# pcbremote.net
KiCad netlist of a schematic drawn in EAGLE
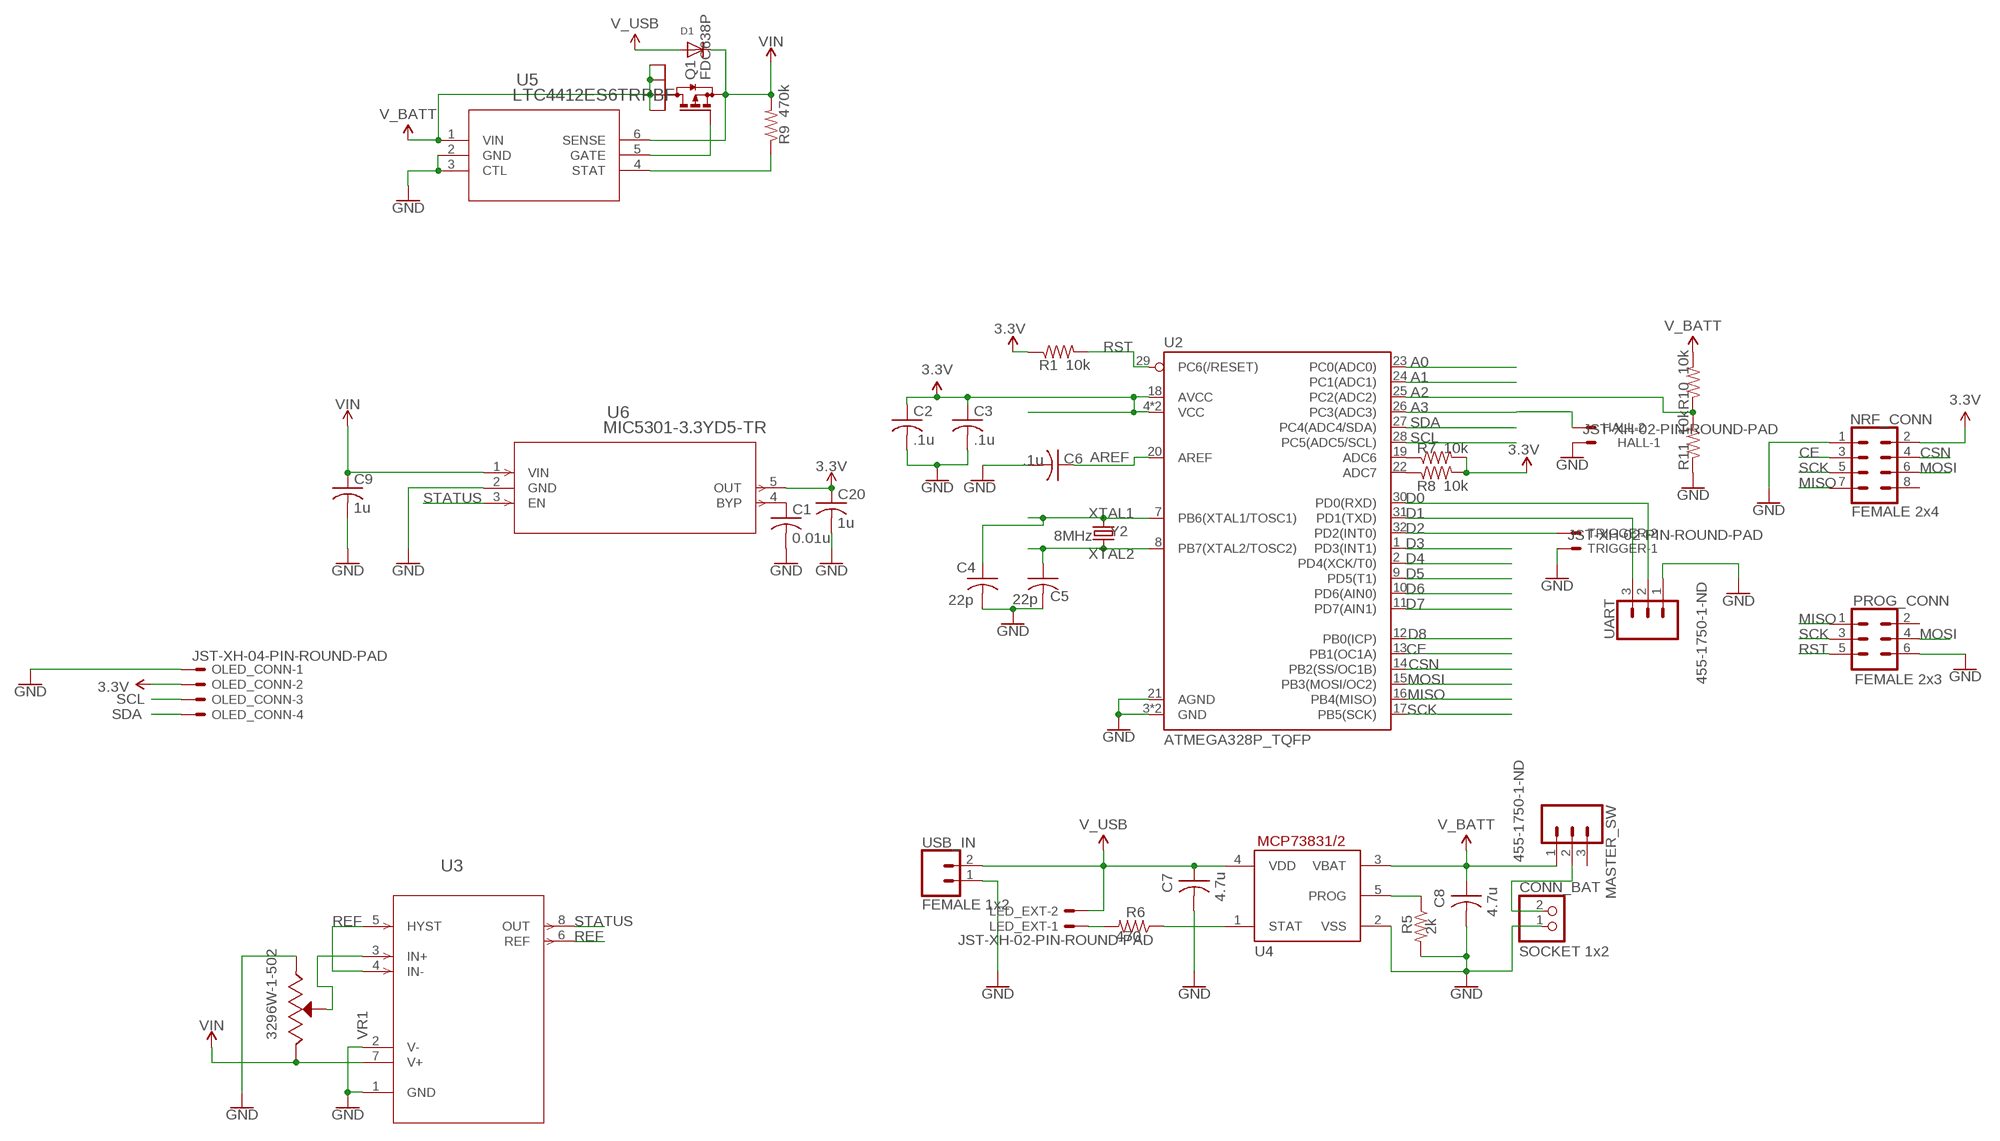
[diagram p0: schematic, sheet 1]

(export (version "E")
  (design (tool "Eeschema 10.0.6"))
  (components
    (comp (ref "C1")
      (value "0.01u")
      (footprint "eagle-import:C0805")
      (libsource (lib "eagle-import") (part "C-USC0805"))
    )
    (comp (ref "C2")
      (value ".1u")
      (footprint "eagle-import:C0805")
      (libsource (lib "eagle-import") (part "C-USC0805"))
    )
    (comp (ref "C3")
      (value ".1u")
      (footprint "eagle-import:C0805")
      (libsource (lib "eagle-import") (part "C-USC0805"))
    )
    (comp (ref "C4")
      (value "22p")
      (footprint "eagle-import:C0805")
      (libsource (lib "eagle-import") (part "C-USC0805"))
    )
    (comp (ref "C5")
      (value "22p")
      (footprint "eagle-import:C0805")
      (libsource (lib "eagle-import") (part "C-USC0805"))
    )
    (comp (ref "C6")
      (value ".1u")
      (footprint "eagle-import:C0805")
      (libsource (lib "eagle-import") (part "C-USC0805"))
    )
    (comp (ref "C7")
      (value "4.7u")
      (footprint "eagle-import:C0805")
      (libsource (lib "eagle-import") (part "C-USC0805"))
    )
    (comp (ref "C8")
      (value "4.7u")
      (footprint "eagle-import:C0805")
      (libsource (lib "eagle-import") (part "C-USC0805"))
    )
    (comp (ref "C9")
      (value "1u")
      (footprint "eagle-import:C0805")
      (libsource (lib "eagle-import") (part "C-USC0805"))
    )
    (comp (ref "C20")
      (value "1u")
      (footprint "eagle-import:C0805")
      (libsource (lib "eagle-import") (part "C-USC0805"))
    )
    (comp (ref "CONN_BAT")
      (value "SOCKET 1x2")
      (footprint "eagle-import:JST-PH-2-THM")
      (libsource (lib "eagle-import") (part "JST_2PIN-THM"))
    )
    (comp (ref "D1")
      (value "DIODESOD-123")
      (footprint "eagle-import:SOD-123")
      (libsource (lib "eagle-import") (part "DIODESOD-123"))
    )
    (comp (ref "HALL")
      (value "JST-XH-02-PIN-ROUND-PAD")
      (footprint "eagle-import:JST-XH-02-PACKAGE-ROUND-PAD")
      (libsource (lib "eagle-import") (part "JST-XH-02-PIN-ROUND-PAD"))
    )
    (comp (ref "LED_EXT")
      (value "JST-XH-02-PIN-ROUND-PAD")
      (footprint "eagle-import:JST-XH-02-PACKAGE-ROUND-PAD")
      (libsource (lib "eagle-import") (part "JST-XH-02-PIN-ROUND-PAD"))
    )
    (comp (ref "MASTER_SW")
      (value "455-1750-1-ND")
      (footprint "eagle-import:1X03")
      (libsource (lib "eagle-import") (part "CONN_03"))
    )
    (comp (ref "NRF_CONN")
      (value "FEMALE 2x4")
      (footprint "eagle-import:2X4")
      (libsource (lib "eagle-import") (part "CONN_04X2"))
    )
    (comp (ref "OLED_CONN")
      (value "JST-XH-04-PIN-ROUND-PAD")
      (footprint "eagle-import:JST-XH-04-PACKAGE-ROUND-PAD")
      (libsource (lib "eagle-import") (part "JST-XH-04-PIN-ROUND-PAD"))
    )
    (comp (ref "PROG_CONN")
      (value "FEMALE 2x3")
      (footprint "eagle-import:2X3")
      (libsource (lib "eagle-import") (part "CONN_03X2FEMALE"))
    )
    (comp (ref "Q1")
      (value "FDC638P")
      (footprint "eagle-import:SSOT-6")
      (fields (field (name "DIGI-KEY_PART_NUMBER") "FDC638PCT-ND") (field (name "MF") "ON Semiconductor"))
      (libsource (lib "eagle-import") (part "FDC638P"))
    )
    (comp (ref "R1")
      (value "10k")
      (footprint "eagle-import:R0805")
      (libsource (lib "eagle-import") (part "R-US_R0805"))
    )
    (comp (ref "R5")
      (value "2k")
      (footprint "eagle-import:R0805")
      (libsource (lib "eagle-import") (part "R-US_R0805"))
    )
    (comp (ref "R6")
      (value "470")
      (footprint "eagle-import:R0805")
      (libsource (lib "eagle-import") (part "R-US_R0805"))
    )
    (comp (ref "R7")
      (value "10k")
      (footprint "eagle-import:R0805")
      (libsource (lib "eagle-import") (part "R-US_R0805"))
    )
    (comp (ref "R8")
      (value "10k")
      (footprint "eagle-import:R0805")
      (libsource (lib "eagle-import") (part "R-US_R0805"))
    )
    (comp (ref "R9")
      (value "470k")
      (footprint "eagle-import:R0805")
      (libsource (lib "eagle-import") (part "R-US_R0805"))
    )
    (comp (ref "R10")
      (value "10k")
      (footprint "eagle-import:R0805")
      (libsource (lib "eagle-import") (part "R-US_R0805"))
    )
    (comp (ref "R11")
      (value "10k")
      (footprint "eagle-import:R0805")
      (libsource (lib "eagle-import") (part "R-US_R0805"))
    )
    (comp (ref "TRIGGER")
      (value "JST-XH-02-PIN-ROUND-PAD")
      (footprint "eagle-import:JST-XH-02-PACKAGE-ROUND-PAD")
      (libsource (lib "eagle-import") (part "JST-XH-02-PIN-ROUND-PAD"))
    )
    (comp (ref "U2")
      (value "ATMEGA328P_TQFP")
      (footprint "eagle-import:TQFP32-08")
      (libsource (lib "eagle-import") (part "ATMEGA328P_TQFP"))
    )
    (comp (ref "U3")
      (value "LTC1540CS8PBF")
      (footprint "eagle-import:SO-8_S_LIT")
      (fields (field (name "MANUFACTURER_PART_NUMBER") "ltc1540cs8#pbf"))
      (libsource (lib "eagle-import") (part "LTC1540CS8PBF"))
    )
    (comp (ref "U4")
      (value "MCP73831/OT")
      (footprint "eagle-import:SOT23-5L")
      (libsource (lib "eagle-import") (part "MCP73831/OT"))
    )
    (comp (ref "U5")
      (value "LTC4412ES6TRPBF")
      (footprint "eagle-import:TSOT-23_S6_LIT")
      (fields (field (name "MANUFACTURER_PART_NUMBER") "LTC4412ES6#TRPBF"))
      (libsource (lib "eagle-import") (part "LTC4412ES6TRPBF"))
    )
    (comp (ref "U6")
      (value "MIC5301-3.3YD5-TR")
      (footprint "eagle-import:TSOT-23-5_D5_MCH")
      (fields (field (name "COPYRIGHT") "Copyright (C) 2018 Accelerated Designs. All rights reserved"))
      (libsource (lib "eagle-import") (part "MIC5301-3.3YD5-TR"))
    )
    (comp (ref "UART")
      (value "455-1750-1-ND")
      (footprint "eagle-import:1X03")
      (libsource (lib "eagle-import") (part "CONN_03"))
    )
    (comp (ref "USB_IN")
      (value "FEMALE 1x2")
      (footprint "eagle-import:1X02")
      (libsource (lib "eagle-import") (part "CONN_02"))
    )
    (comp (ref "VR1")
      (value "3296W-1-502")
      (footprint "eagle-import:TRIM_3296W-1-502")
      (fields (field (name "DIGI-KEY_PART_NUMBER") "3296W-502LF-ND") (field (name "MF") "Bourns"))
      (libsource (lib "eagle-import") (part "3296W-1-502"))
    )
    (comp (ref "Y2")
      (value "8MHz")
      (footprint "eagle-import:CRYSTAL-SMD-5X3.2-4PAD")
      (libsource (lib "eagle-import") (part "CRYSTAL-8MHZSMD-5X3.2"))
    )
  )
  (nets
    (net (code "1") (name "/A0") (class "Default")
      (node (ref "U2") (pin "23") (pinfunction "PC0(ADC0)_23") (pintype "bidirectional"))
    )
    (net (code "2") (name "/A1") (class "Default")
      (node (ref "U2") (pin "24") (pinfunction "PC1(ADC1)_24") (pintype "bidirectional"))
    )
    (net (code "3") (name "/A2") (class "Default")
      (node (ref "R10") (pin "1") (pinfunction "1_1") (pintype "passive"))
      (node (ref "R11") (pin "2") (pinfunction "2_2") (pintype "passive"))
      (node (ref "U2") (pin "25") (pinfunction "PC2(ADC2)_25") (pintype "bidirectional"))
    )
    (net (code "4") (name "/A3") (class "Default")
      (node (ref "HALL") (pin "2") (pinfunction "S_2") (pintype "passive"))
      (node (ref "U2") (pin "26") (pinfunction "PC3(ADC3)_26") (pintype "bidirectional"))
    )
    (net (code "5") (name "/AREF") (class "Default")
      (node (ref "C6") (pin "1") (pinfunction "1_1") (pintype "passive"))
      (node (ref "U2") (pin "20") (pinfunction "AREF_20") (pintype "bidirectional"))
    )
    (net (code "6") (name "/CE") (class "Default")
      (node (ref "NRF_CONN") (pin "3") (pinfunction "3_3") (pintype "passive"))
      (node (ref "U2") (pin "13") (pinfunction "PB1(OC1A)_13") (pintype "bidirectional"))
    )
    (net (code "7") (name "/CSN") (class "Default")
      (node (ref "NRF_CONN") (pin "4") (pinfunction "4_4") (pintype "passive"))
      (node (ref "U2") (pin "14") (pinfunction "PB2(SS/OC1B)_14") (pintype "bidirectional"))
    )
    (net (code "8") (name "/D0") (class "Default")
      (node (ref "U2") (pin "30") (pinfunction "PD0(RXD)_30") (pintype "bidirectional"))
      (node (ref "UART") (pin "2") (pinfunction "2_2") (pintype "passive"))
    )
    (net (code "9") (name "/D1") (class "Default")
      (node (ref "U2") (pin "31") (pinfunction "PD1(TXD)_31") (pintype "bidirectional"))
      (node (ref "UART") (pin "3") (pinfunction "3_3") (pintype "passive"))
    )
    (net (code "10") (name "/D2") (class "Default")
      (node (ref "TRIGGER") (pin "2") (pinfunction "S_2") (pintype "passive"))
      (node (ref "U2") (pin "32") (pinfunction "PD2(INT0)_32") (pintype "bidirectional"))
    )
    (net (code "11") (name "/D3") (class "Default")
      (node (ref "U2") (pin "1") (pinfunction "PD3(INT1)_1") (pintype "bidirectional"))
    )
    (net (code "12") (name "/D4") (class "Default")
      (node (ref "U2") (pin "2") (pinfunction "PD4(XCK/T0)_2") (pintype "bidirectional"))
    )
    (net (code "13") (name "/D5") (class "Default")
      (node (ref "U2") (pin "9") (pinfunction "PD5(T1)_9") (pintype "bidirectional"))
    )
    (net (code "14") (name "/D6") (class "Default")
      (node (ref "U2") (pin "10") (pinfunction "PD6(AIN0)_10") (pintype "bidirectional"))
    )
    (net (code "15") (name "/D7") (class "Default")
      (node (ref "U2") (pin "11") (pinfunction "PD7(AIN1)_11") (pintype "bidirectional"))
    )
    (net (code "16") (name "/D8") (class "Default")
      (node (ref "U2") (pin "12") (pinfunction "PB0(ICP)_12") (pintype "bidirectional"))
    )
    (net (code "17") (name "/MISO") (class "Default")
      (node (ref "NRF_CONN") (pin "7") (pinfunction "7_7") (pintype "passive"))
      (node (ref "PROG_CONN") (pin "1") (pinfunction "1_1") (pintype "bidirectional"))
      (node (ref "U2") (pin "16") (pinfunction "PB4(MISO)_16") (pintype "bidirectional"))
    )
    (net (code "18") (name "/MOSI") (class "Default")
      (node (ref "NRF_CONN") (pin "6") (pinfunction "6_6") (pintype "passive"))
      (node (ref "PROG_CONN") (pin "4") (pinfunction "4_4") (pintype "bidirectional"))
      (node (ref "U2") (pin "15") (pinfunction "PB3(MOSI/OC2)_15") (pintype "bidirectional"))
    )
    (net (code "19") (name "/REF") (class "Default")
      (node (ref "U3") (pin "4") (pinfunction "IN-_4") (pintype "input"))
      (node (ref "U3") (pin "5") (pinfunction "HYST_5") (pintype "input"))
      (node (ref "U3") (pin "6") (pinfunction "REF_6") (pintype "output"))
    )
    (net (code "20") (name "/RST") (class "Default")
      (node (ref "PROG_CONN") (pin "5") (pinfunction "5_5") (pintype "bidirectional"))
      (node (ref "R1") (pin "2") (pinfunction "2_2") (pintype "passive"))
      (node (ref "U2") (pin "29") (pinfunction "PC6(/RESET)_29") (pintype "bidirectional"))
    )
    (net (code "21") (name "/SCK") (class "Default")
      (node (ref "NRF_CONN") (pin "5") (pinfunction "5_5") (pintype "passive"))
      (node (ref "PROG_CONN") (pin "3") (pinfunction "3_3") (pintype "bidirectional"))
      (node (ref "U2") (pin "17") (pinfunction "PB5(SCK)_17") (pintype "bidirectional"))
    )
    (net (code "22") (name "/SCL") (class "Default")
      (node (ref "OLED_CONN") (pin "3") (pinfunction "S_3") (pintype "passive"))
      (node (ref "U2") (pin "28") (pinfunction "PC5(ADC5/SCL)_28") (pintype "bidirectional"))
    )
    (net (code "23") (name "/SDA") (class "Default")
      (node (ref "OLED_CONN") (pin "4") (pinfunction "S_4") (pintype "passive"))
      (node (ref "U2") (pin "27") (pinfunction "PC4(ADC4/SDA)_27") (pintype "bidirectional"))
    )
    (net (code "24") (name "/STATUS") (class "Default")
      (node (ref "U3") (pin "8") (pinfunction "OUT_8") (pintype "output"))
      (node (ref "U6") (pin "3") (pinfunction "EN_3") (pintype "input"))
    )
    (net (code "25") (name "/XTAL1") (class "Default")
      (node (ref "C4") (pin "1") (pinfunction "1_1") (pintype "passive"))
      (node (ref "U2") (pin "7") (pinfunction "PB6(XTAL1/TOSC1)_7") (pintype "bidirectional"))
      (node (ref "Y2") (pin "1") (pinfunction "1_1") (pintype "passive"))
    )
    (net (code "26") (name "/XTAL2") (class "Default")
      (node (ref "C5") (pin "1") (pinfunction "1_1") (pintype "passive"))
      (node (ref "U2") (pin "8") (pinfunction "PB7(XTAL2/TOSC2)_8") (pintype "bidirectional"))
      (node (ref "Y2") (pin "3") (pinfunction "2_3") (pintype "passive"))
    )
    (net (code "27") (name "3.3V") (class "Default")
      (node (ref "C2") (pin "1") (pinfunction "1_1") (pintype "passive"))
      (node (ref "C20") (pin "1") (pinfunction "1_1") (pintype "passive"))
      (node (ref "C3") (pin "1") (pinfunction "1_1") (pintype "passive"))
      (node (ref "NRF_CONN") (pin "2") (pinfunction "2_2") (pintype "passive"))
      (node (ref "OLED_CONN") (pin "2") (pinfunction "S_2") (pintype "passive"))
      (node (ref "R1") (pin "1") (pinfunction "1_1") (pintype "passive"))
      (node (ref "R7") (pin "2") (pinfunction "2_2") (pintype "passive"))
      (node (ref "R8") (pin "2") (pinfunction "2_2") (pintype "passive"))
      (node (ref "U2") (pin "18") (pinfunction "AVCC_18") (pintype "bidirectional"))
      (node (ref "U2") (pin "4") (pinfunction "VCC_4") (pintype "bidirectional"))
      (node (ref "U2") (pin "6") (pinfunction "VCC_6") (pintype "bidirectional"))
      (node (ref "U6") (pin "5") (pinfunction "OUT_5") (pintype "output"))
    )
    (net (code "28") (name "GND") (class "Default")
      (node (ref "C1") (pin "2") (pinfunction "2_2") (pintype "passive"))
      (node (ref "C2") (pin "2") (pinfunction "2_2") (pintype "passive"))
      (node (ref "C20") (pin "2") (pinfunction "2_2") (pintype "passive"))
      (node (ref "C3") (pin "2") (pinfunction "2_2") (pintype "passive"))
      (node (ref "C4") (pin "2") (pinfunction "2_2") (pintype "passive"))
      (node (ref "C5") (pin "2") (pinfunction "2_2") (pintype "passive"))
      (node (ref "C6") (pin "2") (pinfunction "2_2") (pintype "passive"))
      (node (ref "C7") (pin "2") (pinfunction "2_2") (pintype "passive"))
      (node (ref "C8") (pin "2") (pinfunction "2_2") (pintype "passive"))
      (node (ref "C9") (pin "2") (pinfunction "2_2") (pintype "passive"))
      (node (ref "CONN_BAT") (pin "1") (pinfunction "2_1") (pintype "passive"))
      (node (ref "HALL") (pin "1") (pinfunction "S_1") (pintype "passive"))
      (node (ref "NRF_CONN") (pin "1") (pinfunction "1_1") (pintype "passive"))
      (node (ref "OLED_CONN") (pin "1") (pinfunction "S_1") (pintype "passive"))
      (node (ref "PROG_CONN") (pin "6") (pinfunction "6_6") (pintype "bidirectional"))
      (node (ref "R11") (pin "1") (pinfunction "1_1") (pintype "passive"))
      (node (ref "R5") (pin "2") (pinfunction "2_2") (pintype "passive"))
      (node (ref "TRIGGER") (pin "1") (pinfunction "S_1") (pintype "passive"))
      (node (ref "U2") (pin "21") (pinfunction "AGND_21") (pintype "bidirectional"))
      (node (ref "U2") (pin "3") (pinfunction "GND_3") (pintype "bidirectional"))
      (node (ref "U2") (pin "5") (pinfunction "GND_5") (pintype "bidirectional"))
      (node (ref "U3") (pin "1") (pinfunction "GND_1") (pintype "power_in"))
      (node (ref "U3") (pin "2") (pinfunction "V-_2") (pintype "power_in"))
      (node (ref "U4") (pin "2") (pinfunction "VSS_2") (pintype "power_in"))
      (node (ref "U5") (pin "2") (pinfunction "GND_2") (pintype "power_in"))
      (node (ref "U5") (pin "3") (pinfunction "CTL_3") (pintype "input"))
      (node (ref "U6") (pin "2") (pinfunction "GND_2") (pintype "power_in"))
      (node (ref "UART") (pin "1") (pinfunction "1_1") (pintype "passive"))
      (node (ref "USB_IN") (pin "1") (pinfunction "1_1") (pintype "passive"))
      (node (ref "VR1") (pin "3") (pinfunction "CW_3") (pintype "passive"))
    )
    (net (code "29") (name "Net-(CONN_BAT-1)") (class "Default")
      (node (ref "CONN_BAT") (pin "2") (pinfunction "1_2") (pintype "passive"))
      (node (ref "MASTER_SW") (pin "2") (pinfunction "2_2") (pintype "passive"))
    )
    (net (code "30") (name "Net-(LED_EXTA-S)") (class "Default")
      (node (ref "LED_EXT") (pin "1") (pinfunction "S_1") (pintype "passive"))
      (node (ref "R6") (pin "2") (pinfunction "2_2") (pintype "passive"))
    )
    (net (code "31") (name "Net-(Q1-G)") (class "Default")
      (node (ref "Q1") (pin "3") (pinfunction "G_3") (pintype "passive"))
      (node (ref "U5") (pin "5") (pinfunction "GATE_5") (pintype "passive"))
    )
    (net (code "32") (name "Net-(U2-ADC6)") (class "Default")
      (node (ref "R7") (pin "1") (pinfunction "1_1") (pintype "passive"))
      (node (ref "U2") (pin "19") (pinfunction "ADC6_19") (pintype "bidirectional"))
    )
    (net (code "33") (name "Net-(U2-ADC7)") (class "Default")
      (node (ref "R8") (pin "1") (pinfunction "1_1") (pintype "passive"))
      (node (ref "U2") (pin "22") (pinfunction "ADC7_22") (pintype "bidirectional"))
    )
    (net (code "34") (name "Net-(U3-IN+)") (class "Default")
      (node (ref "U3") (pin "3") (pinfunction "IN+_3") (pintype "input"))
      (node (ref "VR1") (pin "2") (pinfunction "WIPER_2") (pintype "passive"))
    )
    (net (code "35") (name "Net-(U4-PROG)") (class "Default")
      (node (ref "R5") (pin "1") (pinfunction "1_1") (pintype "passive"))
      (node (ref "U4") (pin "5") (pinfunction "PROG_5") (pintype "input"))
    )
    (net (code "36") (name "Net-(U4-STAT)") (class "Default")
      (node (ref "R6") (pin "1") (pinfunction "1_1") (pintype "passive"))
      (node (ref "U4") (pin "1") (pinfunction "STAT_1") (pintype "output"))
    )
    (net (code "37") (name "Net-(U5-STAT)") (class "Default")
      (node (ref "R9") (pin "1") (pinfunction "1_1") (pintype "passive"))
      (node (ref "U5") (pin "4") (pinfunction "STAT_4") (pintype "output"))
    )
    (net (code "38") (name "Net-(U6-BYP)") (class "Default")
      (node (ref "C1") (pin "1") (pinfunction "1_1") (pintype "passive"))
      (node (ref "U6") (pin "4") (pinfunction "BYP_4") (pintype "output"))
    )
    (net (code "39") (name "VIN") (class "Default")
      (node (ref "C9") (pin "1") (pinfunction "1_1") (pintype "passive"))
      (node (ref "D1") (pin "C") (pinfunction "C_C") (pintype "passive"))
      (node (ref "Q1") (pin "4") (pinfunction "S_4") (pintype "passive"))
      (node (ref "R9") (pin "2") (pinfunction "2_2") (pintype "passive"))
      (node (ref "U3") (pin "7") (pinfunction "V+_7") (pintype "power_in"))
      (node (ref "U5") (pin "6") (pinfunction "SENSE_6") (pintype "input"))
      (node (ref "U6") (pin "1") (pinfunction "VIN_1") (pintype "input"))
      (node (ref "VR1") (pin "1") (pinfunction "CCW_1") (pintype "passive"))
    )
    (net (code "40") (name "V_BATT") (class "Default")
      (node (ref "C8") (pin "1") (pinfunction "1_1") (pintype "passive"))
      (node (ref "MASTER_SW") (pin "1") (pinfunction "1_1") (pintype "passive"))
      (node (ref "Q1") (pin "1") (pinfunction "D4_1") (pintype "passive"))
      (node (ref "Q1") (pin "2") (pinfunction "D1_2") (pintype "passive"))
      (node (ref "Q1") (pin "5") (pinfunction "D2_5") (pintype "passive"))
      (node (ref "Q1") (pin "6") (pinfunction "D3_6") (pintype "passive"))
      (node (ref "R10") (pin "2") (pinfunction "2_2") (pintype "passive"))
      (node (ref "U4") (pin "3") (pinfunction "VBAT_3") (pintype "bidirectional"))
      (node (ref "U5") (pin "1") (pinfunction "VIN_1") (pintype "input"))
    )
    (net (code "41") (name "V_USB") (class "Default")
      (node (ref "C7") (pin "1") (pinfunction "1_1") (pintype "passive"))
      (node (ref "D1") (pin "A") (pinfunction "A_A") (pintype "passive"))
      (node (ref "LED_EXT") (pin "2") (pinfunction "S_2") (pintype "passive"))
      (node (ref "U4") (pin "4") (pinfunction "VDD_4") (pintype "power_in"))
      (node (ref "USB_IN") (pin "2") (pinfunction "2_2") (pintype "passive"))
    )
    (net (code "42") (name "unconnected-(MASTER_SW-Pad3)") (class "Default")
      (node (ref "MASTER_SW") (pin "3") (pinfunction "3_3") (pintype "passive"))
    )
    (net (code "43") (name "unconnected-(NRF_CONN-Pad8)") (class "Default")
      (node (ref "NRF_CONN") (pin "8") (pinfunction "8_8") (pintype "passive"))
    )
    (net (code "44") (name "unconnected-(PROG_CONN-Pad2)") (class "Default")
      (node (ref "PROG_CONN") (pin "2") (pinfunction "2_2") (pintype "bidirectional"))
    )
  )
)
